# REGENIX_IO_EXPANDER.net
KiCad netlist of a schematic drawn in Altium Designer
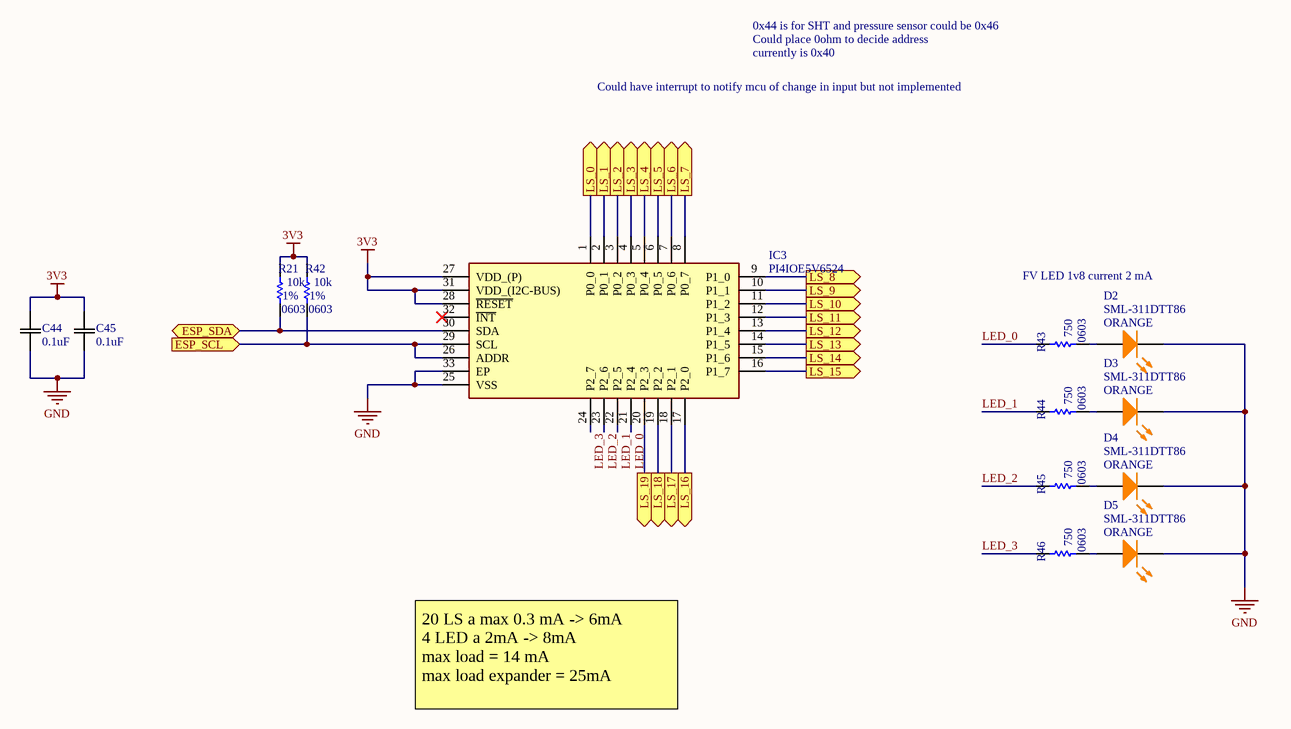
[diagram p0: REGENIX_IO_EXPANDER.SchDoc]

(export (version "E")
  (design (tool "Eeschema 10.0.6"))
  (components
    (comp (ref "C44")
      (value "0.1uF")
      (footprint "CAP_CL10_SAM")
      (description "CAP CER 0.1UF 50V X7R 0603 CL10B104KB8NNWC")
      (libsource (lib "CL10B104KB8NNWC") (part "CL10B104KB8NNWC"))
    )
    (comp (ref "C45")
      (value "0.1uF")
      (footprint "CAP_CL10_SAM")
      (description "CAP CER 0.1UF 50V X7R 0603 CL10B104KB8NNWC")
      (libsource (lib "CL10B104KB8NNWC") (part "CL10B104KB8NNWC"))
    )
    (comp (ref "D2")
      (value "SML-311DTT86")
      (footprint "LED_0603")
      (description "LED - 611nM ORANGE 2mA - 0603")
      (fields
        (field (name "VOLTAGE") "1.8V")
        (field (name "MFG") "ROHM Semiconductor")
        (field (name "ALTIUM_VALUE") "ORANGE")
        (field (name "CREATEDBY") "Jonathan Bouchard")
      )
      (libsource (lib "S7CAS_LIB2023") (part "LED_SML-311DTT86"))
    )
    (comp (ref "D3")
      (value "SML-311DTT86")
      (footprint "LED_0603")
      (description "LED - 611nM ORANGE 2mA - 0603")
      (fields
        (field (name "VOLTAGE") "1.8V")
        (field (name "MFG") "ROHM Semiconductor")
        (field (name "ALTIUM_VALUE") "ORANGE")
        (field (name "CREATEDBY") "Jonathan Bouchard")
      )
      (libsource (lib "S7CAS_LIB2023") (part "LED_SML-311DTT86"))
    )
    (comp (ref "D4")
      (value "SML-311DTT86")
      (footprint "LED_0603")
      (description "LED - 611nM ORANGE 2mA - 0603")
      (fields
        (field (name "VOLTAGE") "1.8V")
        (field (name "MFG") "ROHM Semiconductor")
        (field (name "ALTIUM_VALUE") "ORANGE")
        (field (name "CREATEDBY") "Jonathan Bouchard")
      )
      (libsource (lib "S7CAS_LIB2023") (part "LED_SML-311DTT86"))
    )
    (comp (ref "D5")
      (value "SML-311DTT86")
      (footprint "LED_0603")
      (description "LED - 611nM ORANGE 2mA - 0603")
      (fields
        (field (name "VOLTAGE") "1.8V")
        (field (name "MFG") "ROHM Semiconductor")
        (field (name "ALTIUM_VALUE") "ORANGE")
        (field (name "CREATEDBY") "Jonathan Bouchard")
      )
      (libsource (lib "S7CAS_LIB2023") (part "LED_SML-311DTT86"))
    )
    (comp (ref "IC3")
      (value "PI4IOE5V6524")
      (footprint "SamacSys:QFN50P500X500X80-33N-D")
      (description "Integrated Circuit")
      (libsource (lib "PI4IOE5V6524") (part "PI4IOE5V6524"))
    )
    (comp (ref "R21")
      (value "10k")
      (footprint "RES_0603")
      (description "RES - 0603")
      (fields
        (field (name "PACKAGE") "0603")
        (field (name "PRECISION") "1%")
        (field (name "CREATEDBY") "Jonathan Bouchard")
      )
      (libsource (lib "S7CAS_LIB2023") (part "RES - 0603"))
    )
    (comp (ref "R42")
      (value "10k")
      (footprint "RES_0603")
      (description "RES - 0603")
      (fields
        (field (name "PACKAGE") "0603")
        (field (name "PRECISION") "1%")
        (field (name "CREATEDBY") "Jonathan Bouchard")
      )
      (libsource (lib "S7CAS_LIB2023") (part "RES - 0603"))
    )
    (comp (ref "R43")
      (value "750")
      (footprint "RES_0603")
      (description "RES - 0603")
      (fields (field (name "PACKAGE") "0603") (field (name "CREATEDBY") "Jonathan Bouchard"))
      (libsource (lib "S7CAS_LIB2023") (part "RES - 0603"))
    )
    (comp (ref "R44")
      (value "750")
      (footprint "RES_0603")
      (description "RES - 0603")
      (fields (field (name "PACKAGE") "0603") (field (name "CREATEDBY") "Jonathan Bouchard"))
      (libsource (lib "S7CAS_LIB2023") (part "RES - 0603"))
    )
    (comp (ref "R45")
      (value "750")
      (footprint "RES_0603")
      (description "RES - 0603")
      (fields (field (name "PACKAGE") "0603") (field (name "CREATEDBY") "Jonathan Bouchard"))
      (libsource (lib "S7CAS_LIB2023") (part "RES - 0603"))
    )
    (comp (ref "R46")
      (value "750")
      (footprint "RES_0603")
      (description "RES - 0603")
      (fields (field (name "PACKAGE") "0603") (field (name "CREATEDBY") "Jonathan Bouchard"))
      (libsource (lib "S7CAS_LIB2023") (part "RES - 0603"))
    )
  )
  (nets
    (net (code "1") (name "/ESP_SCL") (class "Default")
      (node (ref "IC3") (pin "26") (pinfunction "ADDR_26") (pintype "passive"))
      (node (ref "IC3") (pin "29") (pinfunction "SCL_29") (pintype "passive"))
      (node (ref "R42") (pin "1") (pinfunction "1_1") (pintype "passive"))
    )
    (net (code "2") (name "/ESP_SDA") (class "Default")
      (node (ref "IC3") (pin "30") (pinfunction "SDA_30") (pintype "passive"))
      (node (ref "R21") (pin "1") (pinfunction "1_1") (pintype "passive"))
    )
    (net (code "3") (name "/LED_0") (class "Default")
      (node (ref "IC3") (pin "21") (pinfunction "P2_4_21") (pintype "passive"))
      (node (ref "R43") (pin "2") (pinfunction "2_2") (pintype "passive"))
    )
    (net (code "4") (name "/LED_1") (class "Default")
      (node (ref "IC3") (pin "22") (pinfunction "P2_5_22") (pintype "passive"))
      (node (ref "R44") (pin "2") (pinfunction "2_2") (pintype "passive"))
    )
    (net (code "5") (name "/LED_2") (class "Default")
      (node (ref "IC3") (pin "23") (pinfunction "P2_6_23") (pintype "passive"))
      (node (ref "R45") (pin "2") (pinfunction "2_2") (pintype "passive"))
    )
    (net (code "6") (name "/LED_3") (class "Default")
      (node (ref "IC3") (pin "24") (pinfunction "P2_7_24") (pintype "passive"))
      (node (ref "R46") (pin "2") (pinfunction "2_2") (pintype "passive"))
    )
    (net (code "7") (name "/LS_0") (class "Default")
      (node (ref "IC3") (pin "1") (pinfunction "P0_0_1") (pintype "passive"))
    )
    (net (code "8") (name "/LS_1") (class "Default")
      (node (ref "IC3") (pin "2") (pinfunction "P0_1_2") (pintype "passive"))
    )
    (net (code "9") (name "/LS_2") (class "Default")
      (node (ref "IC3") (pin "3") (pinfunction "P0_2_3") (pintype "passive"))
    )
    (net (code "10") (name "/LS_3") (class "Default")
      (node (ref "IC3") (pin "4") (pinfunction "P0_3_4") (pintype "passive"))
    )
    (net (code "11") (name "/LS_4") (class "Default")
      (node (ref "IC3") (pin "5") (pinfunction "P0_4_5") (pintype "passive"))
    )
    (net (code "12") (name "/LS_5") (class "Default")
      (node (ref "IC3") (pin "6") (pinfunction "P0_5_6") (pintype "passive"))
    )
    (net (code "13") (name "/LS_6") (class "Default")
      (node (ref "IC3") (pin "7") (pinfunction "P0_6_7") (pintype "passive"))
    )
    (net (code "14") (name "/LS_7") (class "Default")
      (node (ref "IC3") (pin "8") (pinfunction "P0_7_8") (pintype "passive"))
    )
    (net (code "15") (name "/LS_8") (class "Default")
      (node (ref "IC3") (pin "9") (pinfunction "P1_0_9") (pintype "passive"))
    )
    (net (code "16") (name "/LS_9") (class "Default")
      (node (ref "IC3") (pin "10") (pinfunction "P1_1_10") (pintype "passive"))
    )
    (net (code "17") (name "/LS_10") (class "Default")
      (node (ref "IC3") (pin "11") (pinfunction "P1_2_11") (pintype "passive"))
    )
    (net (code "18") (name "/LS_11") (class "Default")
      (node (ref "IC3") (pin "12") (pinfunction "P1_3_12") (pintype "passive"))
    )
    (net (code "19") (name "/LS_12") (class "Default")
      (node (ref "IC3") (pin "13") (pinfunction "P1_4_13") (pintype "passive"))
    )
    (net (code "20") (name "/LS_13") (class "Default")
      (node (ref "IC3") (pin "14") (pinfunction "P1_5_14") (pintype "passive"))
    )
    (net (code "21") (name "/LS_14") (class "Default")
      (node (ref "IC3") (pin "15") (pinfunction "P1_6_15") (pintype "passive"))
    )
    (net (code "22") (name "/LS_15") (class "Default")
      (node (ref "IC3") (pin "16") (pinfunction "P1_7_16") (pintype "passive"))
    )
    (net (code "23") (name "/LS_16") (class "Default")
      (node (ref "IC3") (pin "17") (pinfunction "P2_0_17") (pintype "passive"))
    )
    (net (code "24") (name "/LS_17") (class "Default")
      (node (ref "IC3") (pin "18") (pinfunction "P2_1_18") (pintype "passive"))
    )
    (net (code "25") (name "/LS_18") (class "Default")
      (node (ref "IC3") (pin "19") (pinfunction "P2_2_19") (pintype "passive"))
    )
    (net (code "26") (name "/LS_19") (class "Default")
      (node (ref "IC3") (pin "20") (pinfunction "P2_3_20") (pintype "passive"))
    )
    (net (code "27") (name "3V3") (class "Default")
      (node (ref "C44") (pin "2") (pinfunction "2_2") (pintype "passive"))
      (node (ref "C45") (pin "2") (pinfunction "2_2") (pintype "passive"))
      (node (ref "IC3") (pin "27") (pinfunction "VDD_(P)_27") (pintype "passive"))
      (node (ref "IC3") (pin "28") (pinfunction "~{RESET}_28") (pintype "passive"))
      (node (ref "IC3") (pin "31") (pinfunction "VDD_(I2C-BUS)_31") (pintype "passive"))
      (node (ref "R21") (pin "2") (pinfunction "2_2") (pintype "passive"))
      (node (ref "R42") (pin "2") (pinfunction "2_2") (pintype "passive"))
    )
    (net (code "28") (name "GND") (class "Default")
      (node (ref "C44") (pin "1") (pinfunction "1_1") (pintype "passive"))
      (node (ref "C45") (pin "1") (pinfunction "1_1") (pintype "passive"))
      (node (ref "D2") (pin "K") (pinfunction "K_K") (pintype "passive"))
      (node (ref "D3") (pin "K") (pinfunction "K_K") (pintype "passive"))
      (node (ref "D4") (pin "K") (pinfunction "K_K") (pintype "passive"))
      (node (ref "D5") (pin "K") (pinfunction "K_K") (pintype "passive"))
      (node (ref "IC3") (pin "25") (pinfunction "VSS_25") (pintype "passive"))
      (node (ref "IC3") (pin "33") (pinfunction "EP_33") (pintype "passive"))
    )
    (net (code "29") (name "Net-(D2-PadA)") (class "Default")
      (node (ref "D2") (pin "A") (pinfunction "A_A") (pintype "passive"))
      (node (ref "R43") (pin "1") (pinfunction "1_1") (pintype "passive"))
    )
    (net (code "30") (name "Net-(D3-PadA)") (class "Default")
      (node (ref "D3") (pin "A") (pinfunction "A_A") (pintype "passive"))
      (node (ref "R44") (pin "1") (pinfunction "1_1") (pintype "passive"))
    )
    (net (code "31") (name "Net-(D4-PadA)") (class "Default")
      (node (ref "D4") (pin "A") (pinfunction "A_A") (pintype "passive"))
      (node (ref "R45") (pin "1") (pinfunction "1_1") (pintype "passive"))
    )
    (net (code "32") (name "Net-(D5-PadA)") (class "Default")
      (node (ref "D5") (pin "A") (pinfunction "A_A") (pintype "passive"))
      (node (ref "R46") (pin "1") (pinfunction "1_1") (pintype "passive"))
    )
    (net (code "33") (name "unconnected-(IC3-~{INT}-Pad32)") (class "Default")
      (node (ref "IC3") (pin "32") (pinfunction "~{INT}_32") (pintype "passive+no_connect"))
    )
  )
)
